# IR_LEDS.net
KiCad netlist of a schematic drawn in Altium Designer
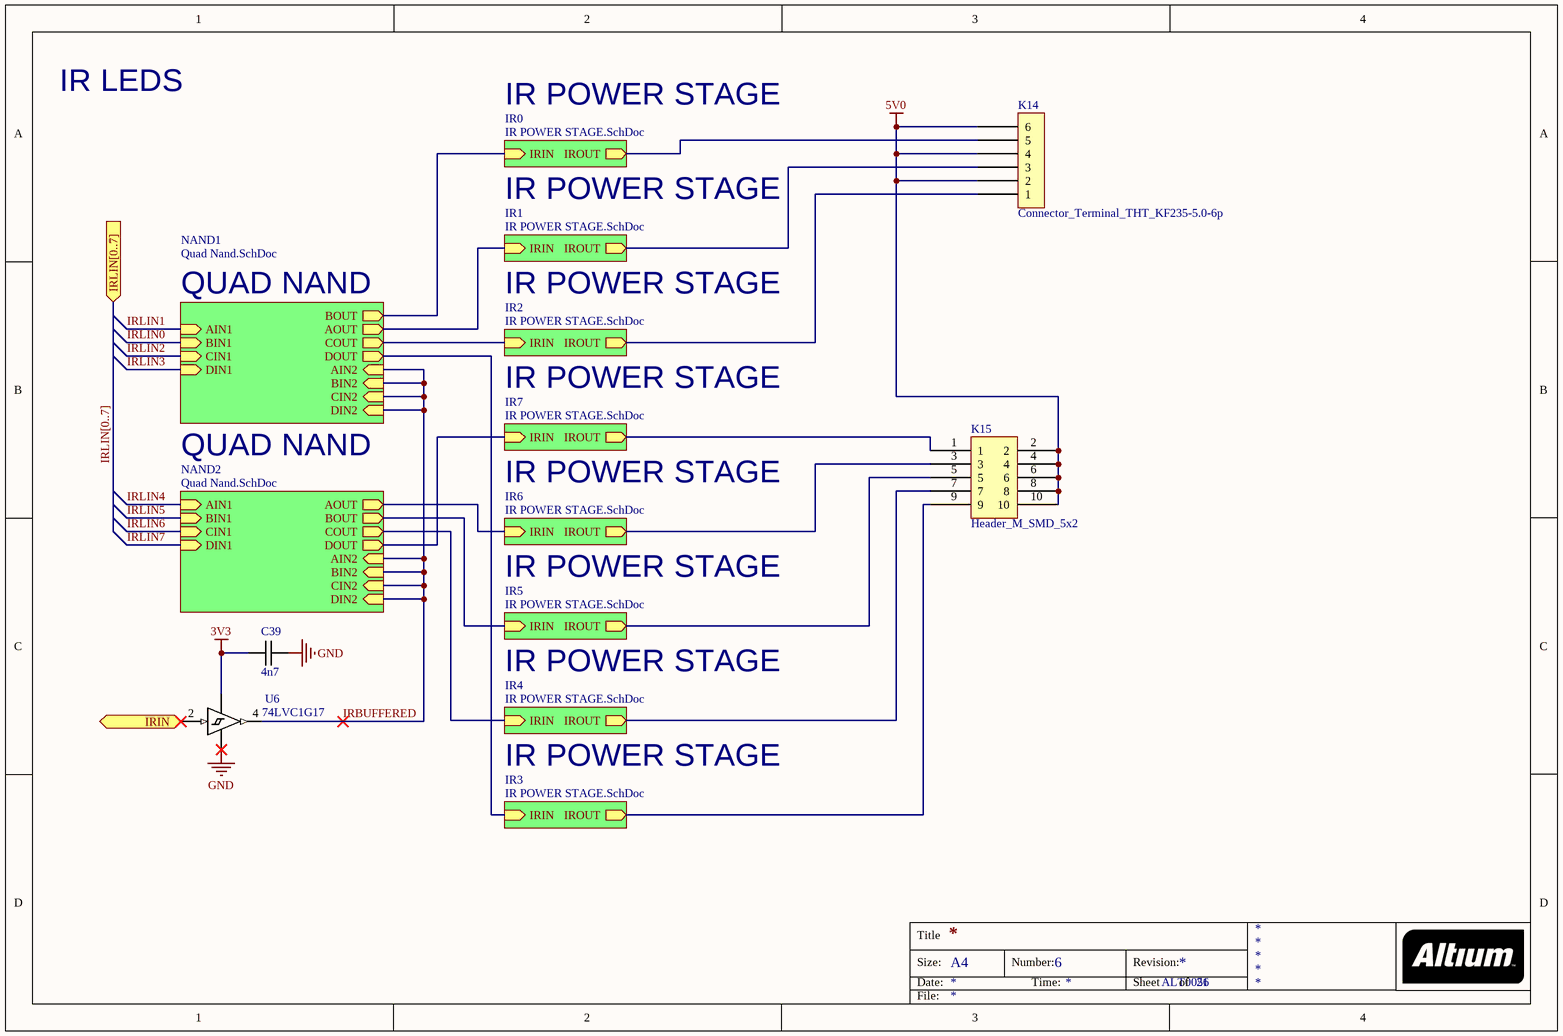
[diagram p0: IR LEDS.SchDoc]

(export (version "E")
  (design (tool "Eeschema 10.0.6"))
  (components
    (comp (ref "C39")
      (value "4n7")
      (footprint "0603C-TBD")
      (description "CAPACITOR 0603 CERAMIC")
      (libsource (lib "RVA_Altium_Library") (part "0603C-4N7"))
    )
    (comp (ref "K14")
      (value "Connector_Terminal_THT_KF235-5.0-6p")
      (footprint "KF235-5.0-6p")
      (libsource (lib "RVA_Altium_Library") (part "Connector_Terminal_THT_KF235-5.0-6p"))
    )
    (comp (ref "K15")
      (value "Header_M_SMD_5x2")
      (footprint "Header_Male_2.54 5x2")
      (description "SMD Header 5x2")
      (libsource (lib "RVA_Altium_Library") (part "Header_M_SMD_5x2"))
    )
    (comp (ref "U6")
      (value "74LVC1G17")
      (footprint "SOT-353")
      (description "Single buffer")
      (libsource (lib "RVA_Altium_Library") (part "74LVC1G17"))
    )
  )
  (nets
    (net (code "1") (name "/AIN2") (class "Default")
      (node (ref "U6") (pin "4") (pinfunction "Y_4") (pintype "output"))
    )
    (net (code "11") (name "/IRIN") (class "Default")
      (node (ref "U6") (pin "2") (pinfunction "A_2") (pintype "input+no_connect"))
    )
    (net (code "21") (name "/IROUT") (class "Default")
      (node (ref "K14") (pin "3") (pinfunction "3_3") (pintype "passive"))
    )
    (net (code "22") (name "/IROUT_1") (class "Default")
      (node (ref "K15") (pin "5") (pinfunction "5_5") (pintype "passive"))
    )
    (net (code "23") (name "/IROUT_2") (class "Default")
      (node (ref "K15") (pin "7") (pinfunction "7_7") (pintype "passive"))
    )
    (net (code "24") (name "/IROUT_3") (class "Default")
      (node (ref "K15") (pin "9") (pinfunction "9_9") (pintype "passive"))
    )
    (net (code "25") (name "/IROUT_4") (class "Default")
      (node (ref "K14") (pin "1") (pinfunction "1_1") (pintype "passive"))
    )
    (net (code "26") (name "/IROUT_5") (class "Default")
      (node (ref "K15") (pin "1") (pinfunction "1_1") (pintype "passive"))
    )
    (net (code "27") (name "/IROUT_6") (class "Default")
      (node (ref "K15") (pin "3") (pinfunction "3_3") (pintype "passive"))
    )
    (net (code "28") (name "/IROUT_7") (class "Default")
      (node (ref "K14") (pin "5") (pinfunction "5_5") (pintype "passive"))
    )
    (net (code "29") (name "3V3") (class "Default")
      (node (ref "C39") (pin "1") (pintype "passive"))
      (node (ref "U6") (pin "5") (pinfunction "VCC_5") (pintype "passive"))
    )
    (net (code "30") (name "5V0") (class "Default")
      (node (ref "K14") (pin "2") (pinfunction "2_2") (pintype "passive"))
      (node (ref "K14") (pin "4") (pinfunction "4_4") (pintype "passive"))
      (node (ref "K14") (pin "6") (pinfunction "6_6") (pintype "passive"))
      (node (ref "K15") (pin "10") (pinfunction "10_10") (pintype "passive"))
      (node (ref "K15") (pin "2") (pinfunction "2_2") (pintype "passive"))
      (node (ref "K15") (pin "4") (pinfunction "4_4") (pintype "passive"))
      (node (ref "K15") (pin "6") (pinfunction "6_6") (pintype "passive"))
      (node (ref "K15") (pin "8") (pinfunction "8_8") (pintype "passive"))
    )
    (net (code "31") (name "GND") (class "Default")
      (node (ref "C39") (pin "2") (pintype "passive"))
      (node (ref "U6") (pin "3") (pinfunction "GND_3") (pintype "power_in"))
    )
  )
)
